# labwiz-module_t420-v0_2.net
KiCad netlist of a schematic drawn in EAGLE
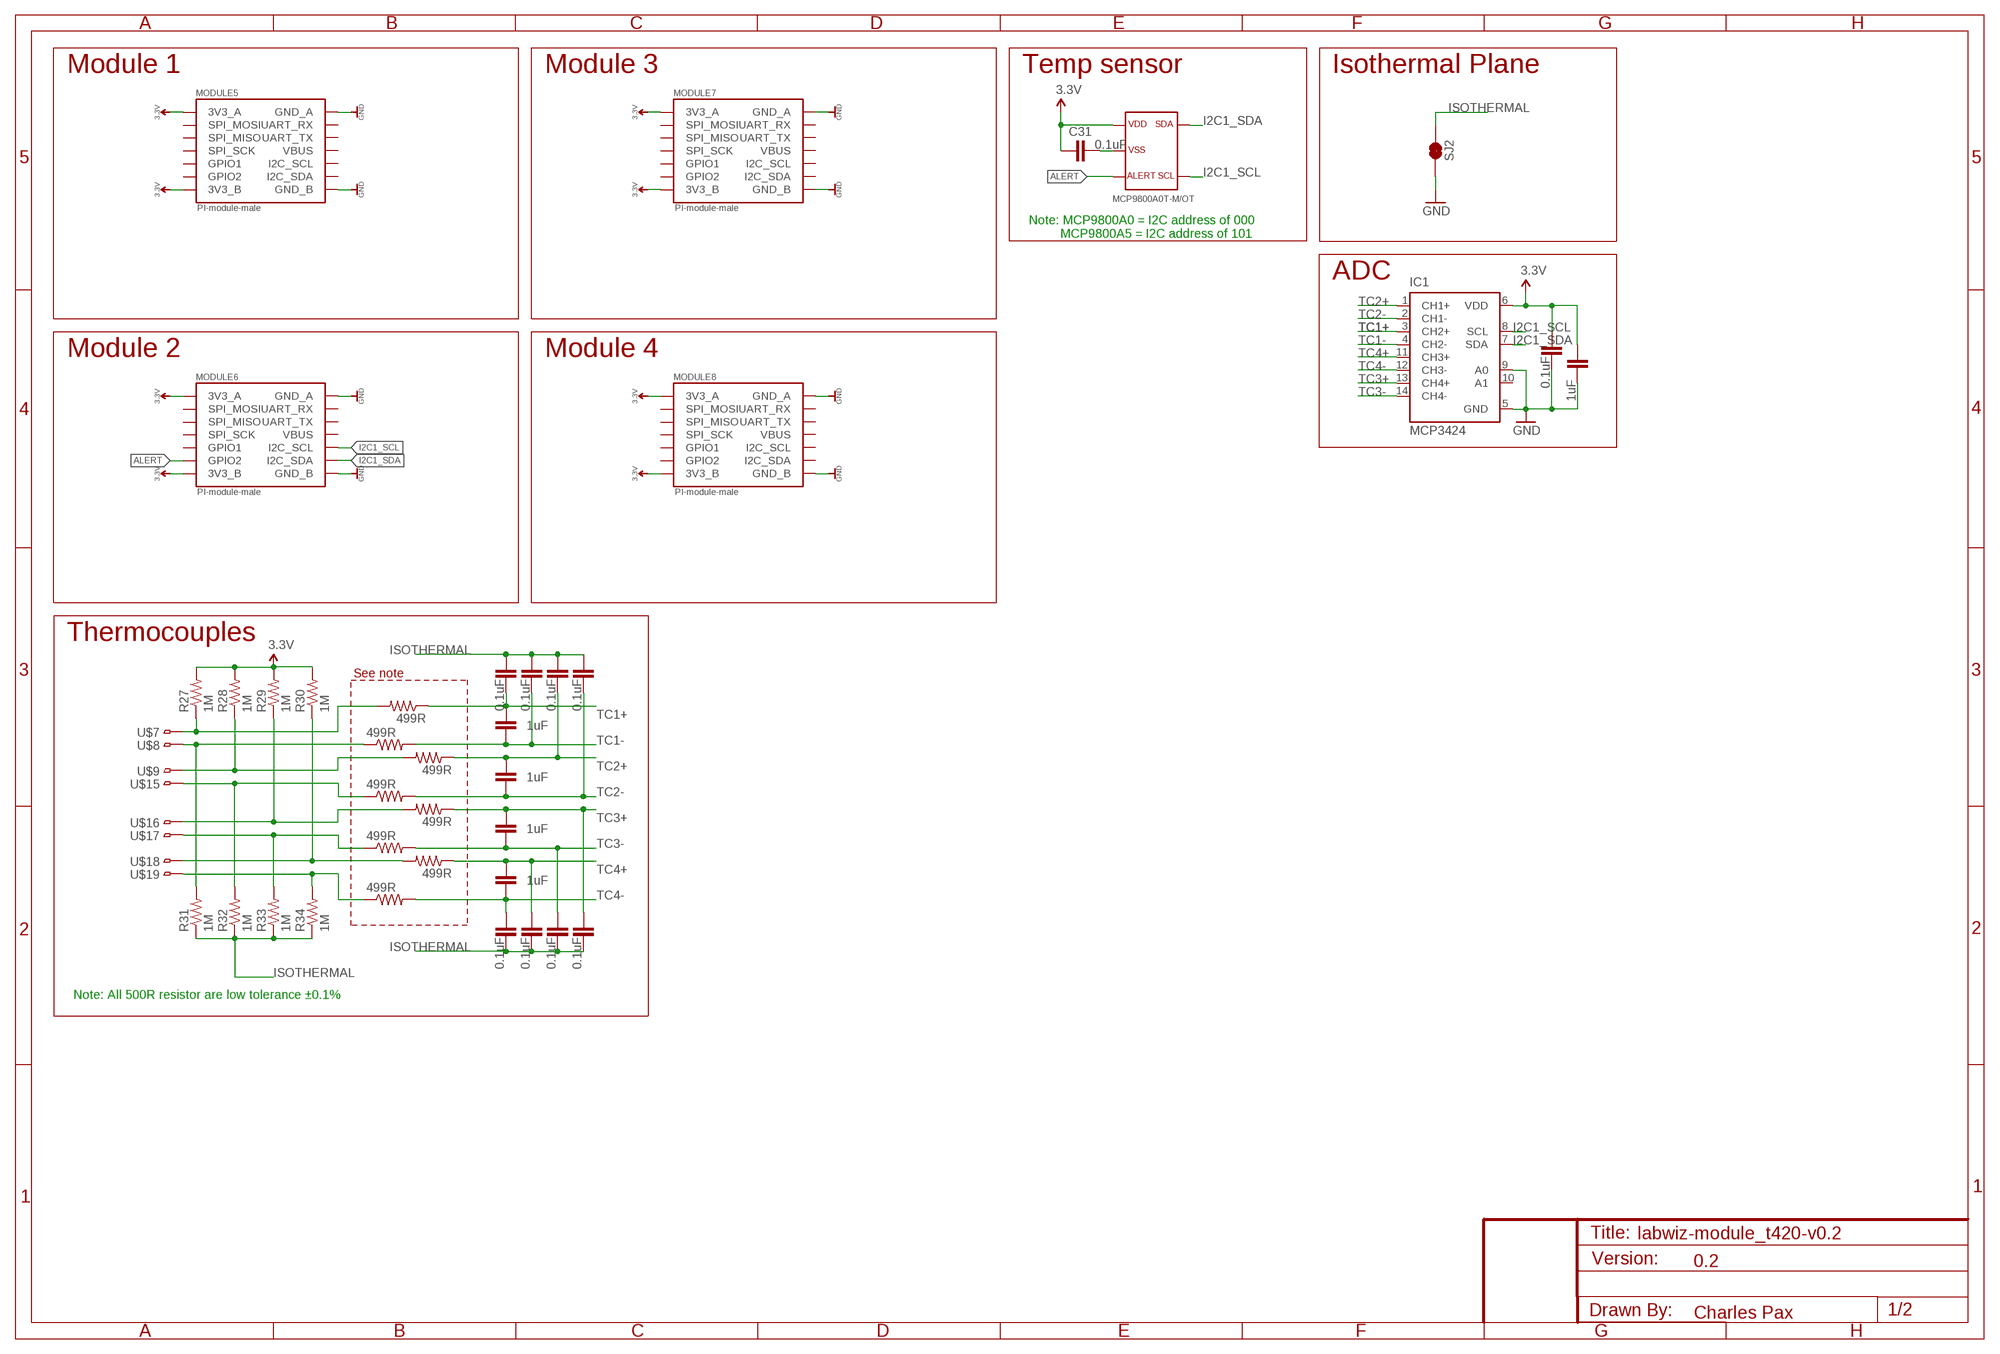
[diagram p0: schematic, sheet 1]

(export (version "E")
  (design (tool "Eeschema 10.0.6"))
  (components
    (comp (ref "C7")
      (value "1uF")
      (footprint "eagle-import:SPARKFUN-CAPACITORS_0603-CAP")
      (libsource (lib "eagle-import") (part "SPARKFUN-CAPACITORS_CAP0603-CAP"))
    )
    (comp (ref "C8")
      (value "1uF")
      (footprint "eagle-import:SPARKFUN-CAPACITORS_0603-CAP")
      (libsource (lib "eagle-import") (part "SPARKFUN-CAPACITORS_CAP0603-CAP"))
    )
    (comp (ref "C10")
      (value "1uF")
      (footprint "eagle-import:SPARKFUN-CAPACITORS_0603-CAP")
      (libsource (lib "eagle-import") (part "SPARKFUN-CAPACITORS_CAP0603-CAP"))
    )
    (comp (ref "C11")
      (value "1uF")
      (footprint "eagle-import:SPARKFUN-CAPACITORS_0603-CAP")
      (libsource (lib "eagle-import") (part "SPARKFUN-CAPACITORS_CAP0603-CAP"))
    )
    (comp (ref "C13")
      (value "0.1uF")
      (footprint "eagle-import:SPARKFUN-CAPACITORS_0603-CAP")
      (libsource (lib "eagle-import") (part "SPARKFUN-CAPACITORS_CAP0603-CAP"))
    )
    (comp (ref "C14")
      (value "0.1uF")
      (footprint "eagle-import:SPARKFUN-CAPACITORS_0603-CAP")
      (libsource (lib "eagle-import") (part "SPARKFUN-CAPACITORS_CAP0603-CAP"))
    )
    (comp (ref "C15")
      (value "0.1uF")
      (footprint "eagle-import:SPARKFUN-CAPACITORS_0603-CAP")
      (libsource (lib "eagle-import") (part "SPARKFUN-CAPACITORS_CAP0603-CAP"))
    )
    (comp (ref "C16")
      (value "0.1uF")
      (footprint "eagle-import:SPARKFUN-CAPACITORS_0603-CAP")
      (libsource (lib "eagle-import") (part "SPARKFUN-CAPACITORS_CAP0603-CAP"))
    )
    (comp (ref "C17")
      (value "0.1uF")
      (footprint "eagle-import:SPARKFUN-CAPACITORS_0603-CAP")
      (libsource (lib "eagle-import") (part "SPARKFUN-CAPACITORS_CAP0603-CAP"))
    )
    (comp (ref "C24")
      (value "0.1uF")
      (footprint "eagle-import:SPARKFUN-CAPACITORS_0603-CAP")
      (libsource (lib "eagle-import") (part "SPARKFUN-CAPACITORS_CAP0603-CAP"))
    )
    (comp (ref "C25")
      (value "0.1uF")
      (footprint "eagle-import:SPARKFUN-CAPACITORS_0603-CAP")
      (libsource (lib "eagle-import") (part "SPARKFUN-CAPACITORS_CAP0603-CAP"))
    )
    (comp (ref "C29")
      (value "0.1uF")
      (footprint "eagle-import:SPARKFUN-CAPACITORS_0603-CAP")
      (libsource (lib "eagle-import") (part "SPARKFUN-CAPACITORS_CAP0603-CAP"))
    )
    (comp (ref "C30")
      (value "1uF")
      (footprint "eagle-import:SPARKFUN-CAPACITORS_0603-CAP")
      (libsource (lib "eagle-import") (part "SPARKFUN-CAPACITORS_CAP0603-CAP"))
    )
    (comp (ref "C31")
      (value "0.1uF")
      (footprint "eagle-import:SPARKFUN-CAPACITORS_0603-CAP")
      (libsource (lib "eagle-import") (part "SPARKFUN-CAPACITORS_CAP0603-CAP"))
    )
    (comp (ref "C37")
      (value "0.1uF")
      (footprint "eagle-import:SPARKFUN-CAPACITORS_0603-CAP")
      (libsource (lib "eagle-import") (part "SPARKFUN-CAPACITORS_CAP0603-CAP"))
    )
    (comp (ref "IC1")
      (value "MCP3424")
      (footprint "eagle-import:SO14")
      (fields (field (name "MF") "Microchip Technology") (field (name "MPN") "MCP3424-E/SL"))
      (libsource (lib "eagle-import") (part "MCP3424"))
    )
    (comp (ref "MODULE5")
      (value "PI-module-male")
      (footprint "eagle-import:M07X2_2MM_EDGE")
      (fields (field (name "MF") "Pax Instruments") (field (name "MPN") "PIxxxx"))
      (libsource (lib "eagle-import") (part "PAX_MODULE_EDGE_MALE_MODULE"))
    )
    (comp (ref "MODULE6")
      (value "PI-module-male")
      (footprint "eagle-import:M07X2_2MM_EDGE")
      (fields (field (name "MF") "Pax Instruments") (field (name "MPN") "PIxxxx"))
      (libsource (lib "eagle-import") (part "PAX_MODULE_EDGE_MALE_MODULE"))
    )
    (comp (ref "MODULE7")
      (value "PI-module-male")
      (footprint "eagle-import:M07X2_2MM_EDGE")
      (fields (field (name "MF") "Pax Instruments") (field (name "MPN") "PIxxxx"))
      (libsource (lib "eagle-import") (part "PAX_MODULE_EDGE_MALE_MODULE"))
    )
    (comp (ref "MODULE8")
      (value "PI-module-male")
      (footprint "eagle-import:M07X2_2MM_EDGE")
      (fields (field (name "MF") "Pax Instruments") (field (name "MPN") "PIxxxx"))
      (libsource (lib "eagle-import") (part "PAX_MODULE_EDGE_MALE_MODULE"))
    )
    (comp (ref "R27")
      (value "1M")
      (footprint "eagle-import:SPARKFUN-RESISTORS_0603-RES")
      (libsource (lib "eagle-import") (part "SPARKFUN-RESISTORS_RESISTOR0603-RES"))
    )
    (comp (ref "R28")
      (value "1M")
      (footprint "eagle-import:SPARKFUN-RESISTORS_0603-RES")
      (libsource (lib "eagle-import") (part "SPARKFUN-RESISTORS_RESISTOR0603-RES"))
    )
    (comp (ref "R29")
      (value "1M")
      (footprint "eagle-import:SPARKFUN-RESISTORS_0603-RES")
      (libsource (lib "eagle-import") (part "SPARKFUN-RESISTORS_RESISTOR0603-RES"))
    )
    (comp (ref "R30")
      (value "1M")
      (footprint "eagle-import:SPARKFUN-RESISTORS_0603-RES")
      (libsource (lib "eagle-import") (part "SPARKFUN-RESISTORS_RESISTOR0603-RES"))
    )
    (comp (ref "R31")
      (value "1M")
      (footprint "eagle-import:SPARKFUN-RESISTORS_0603-RES")
      (libsource (lib "eagle-import") (part "SPARKFUN-RESISTORS_RESISTOR0603-RES"))
    )
    (comp (ref "R32")
      (value "1M")
      (footprint "eagle-import:SPARKFUN-RESISTORS_0603-RES")
      (libsource (lib "eagle-import") (part "SPARKFUN-RESISTORS_RESISTOR0603-RES"))
    )
    (comp (ref "R33")
      (value "1M")
      (footprint "eagle-import:SPARKFUN-RESISTORS_0603-RES")
      (libsource (lib "eagle-import") (part "SPARKFUN-RESISTORS_RESISTOR0603-RES"))
    )
    (comp (ref "R34")
      (value "1M")
      (footprint "eagle-import:SPARKFUN-RESISTORS_0603-RES")
      (libsource (lib "eagle-import") (part "SPARKFUN-RESISTORS_RESISTOR0603-RES"))
    )
    (comp (ref "R35")
      (value "499R")
      (footprint "eagle-import:SPARKFUN-RESISTORS_0603-RES")
      (fields (field (name "MF") "Vishay") (field (name "MPN") "TNPW0603499RBEEA"))
      (libsource (lib "eagle-import") (part "SPARKFUN-RESISTORS_RESISTOR0603-RES"))
    )
    (comp (ref "R36")
      (value "499R")
      (footprint "eagle-import:SPARKFUN-RESISTORS_0603-RES")
      (fields (field (name "MF") "Vishay") (field (name "MPN") "TNPW0603499RBEEA"))
      (libsource (lib "eagle-import") (part "SPARKFUN-RESISTORS_RESISTOR0603-RES"))
    )
    (comp (ref "R37")
      (value "499R")
      (footprint "eagle-import:SPARKFUN-RESISTORS_0603-RES")
      (fields (field (name "MF") "Vishay") (field (name "MPN") "TNPW0603499RBEEA"))
      (libsource (lib "eagle-import") (part "SPARKFUN-RESISTORS_RESISTOR0603-RES"))
    )
    (comp (ref "R38")
      (value "499R")
      (footprint "eagle-import:SPARKFUN-RESISTORS_0603-RES")
      (fields (field (name "MF") "Vishay") (field (name "MPN") "TNPW0603499RBEEA"))
      (libsource (lib "eagle-import") (part "SPARKFUN-RESISTORS_RESISTOR0603-RES"))
    )
    (comp (ref "R39")
      (value "499R")
      (footprint "eagle-import:SPARKFUN-RESISTORS_0603-RES")
      (fields (field (name "MF") "Vishay") (field (name "MPN") "TNPW0603499RBEEA"))
      (libsource (lib "eagle-import") (part "SPARKFUN-RESISTORS_RESISTOR0603-RES"))
    )
    (comp (ref "R40")
      (value "499R")
      (footprint "eagle-import:SPARKFUN-RESISTORS_0603-RES")
      (fields (field (name "MF") "Vishay") (field (name "MPN") "TNPW0603499RBEEA"))
      (libsource (lib "eagle-import") (part "SPARKFUN-RESISTORS_RESISTOR0603-RES"))
    )
    (comp (ref "R41")
      (value "499R")
      (footprint "eagle-import:SPARKFUN-RESISTORS_0603-RES")
      (fields (field (name "MF") "Vishay") (field (name "MPN") "TNPW0603499RBEEA"))
      (libsource (lib "eagle-import") (part "SPARKFUN-RESISTORS_RESISTOR0603-RES"))
    )
    (comp (ref "R42")
      (value "499R")
      (footprint "eagle-import:SPARKFUN-RESISTORS_0603-RES")
      (fields (field (name "MF") "Vishay") (field (name "MPN") "TNPW0603499RBEEA"))
      (libsource (lib "eagle-import") (part "SPARKFUN-RESISTORS_RESISTOR0603-RES"))
    )
    (comp (ref "SJ2")
      (value "JUMPER-PAD-2-NC_BY_TRACE")
      (footprint "eagle-import:PAD-JUMPER-2-NC_BY_TRACE_YES_SILK")
      (libsource (lib "eagle-import") (part "JUMPER-PAD-2-NC_BY_TRACE"))
    )
    (comp (ref "U$7")
      (value "TC-MINI-SINGLE")
      (footprint "eagle-import:TC-CLIP-SINGLE")
      (fields (field (name "MF") "Pax Instrument") (field (name "MPN") "Thermo-clip2"))
      (libsource (lib "eagle-import") (part "TC-MINI-SINGLE"))
    )
    (comp (ref "U$8")
      (value "TC-MINI-SINGLE")
      (footprint "eagle-import:TC-CLIP-SINGLE")
      (fields (field (name "MF") "Pax Instrument") (field (name "MPN") "Thermo-clip2"))
      (libsource (lib "eagle-import") (part "TC-MINI-SINGLE"))
    )
    (comp (ref "U$9")
      (value "TC-MINI-SINGLE")
      (footprint "eagle-import:TC-CLIP-SINGLE")
      (fields (field (name "MF") "Pax Instrument") (field (name "MPN") "Thermo-clip2"))
      (libsource (lib "eagle-import") (part "TC-MINI-SINGLE"))
    )
    (comp (ref "U$15")
      (value "TC-MINI-SINGLE")
      (footprint "eagle-import:TC-CLIP-SINGLE")
      (fields (field (name "MF") "Pax Instrument") (field (name "MPN") "Thermo-clip2"))
      (libsource (lib "eagle-import") (part "TC-MINI-SINGLE"))
    )
    (comp (ref "U$16")
      (value "TC-MINI-SINGLE")
      (footprint "eagle-import:TC-CLIP-SINGLE")
      (fields (field (name "MF") "Pax Instrument") (field (name "MPN") "Thermo-clip2"))
      (libsource (lib "eagle-import") (part "TC-MINI-SINGLE"))
    )
    (comp (ref "U$17")
      (value "TC-MINI-SINGLE")
      (footprint "eagle-import:TC-CLIP-SINGLE")
      (fields (field (name "MF") "Pax Instrument") (field (name "MPN") "Thermo-clip2"))
      (libsource (lib "eagle-import") (part "TC-MINI-SINGLE"))
    )
    (comp (ref "U$18")
      (value "TC-MINI-SINGLE")
      (footprint "eagle-import:TC-CLIP-SINGLE")
      (fields (field (name "MF") "Pax Instrument") (field (name "MPN") "Thermo-clip2"))
      (libsource (lib "eagle-import") (part "TC-MINI-SINGLE"))
    )
    (comp (ref "U$19")
      (value "TC-MINI-SINGLE")
      (footprint "eagle-import:TC-CLIP-SINGLE")
      (fields (field (name "MF") "Pax Instrument") (field (name "MPN") "Thermo-clip2"))
      (libsource (lib "eagle-import") (part "TC-MINI-SINGLE"))
    )
    (comp (ref "U1")
      (value "MCP9800")
      (footprint "eagle-import:SOT23-5L")
      (fields (field (name "MF") "Microchip Technology") (field (name "MPN") "MCP9800A0T-M/OT"))
      (libsource (lib "eagle-import") (part "MCP9800"))
    )
  )
  (nets
    (net (code "1") (name "3.3V") (class "Default")
      (node (ref "C29") (pin "1") (pinfunction "1_1") (pintype "passive"))
      (node (ref "C30") (pin "1") (pinfunction "1_1") (pintype "passive"))
      (node (ref "C31") (pin "1") (pinfunction "1_1") (pintype "passive"))
      (node (ref "IC1") (pin "6") (pinfunction "VDD_6") (pintype "power_in"))
      (node (ref "MODULE5") (pin "P$1") (pinfunction "3V3_B_P$1") (pintype "bidirectional"))
      (node (ref "MODULE5") (pin "P$13") (pinfunction "3V3_A_P$13") (pintype "power_in"))
      (node (ref "MODULE6") (pin "P$1") (pinfunction "3V3_B_P$1") (pintype "bidirectional"))
      (node (ref "MODULE6") (pin "P$13") (pinfunction "3V3_A_P$13") (pintype "power_in"))
      (node (ref "MODULE7") (pin "P$1") (pinfunction "3V3_B_P$1") (pintype "bidirectional"))
      (node (ref "MODULE7") (pin "P$13") (pinfunction "3V3_A_P$13") (pintype "power_in"))
      (node (ref "MODULE8") (pin "P$1") (pinfunction "3V3_B_P$1") (pintype "bidirectional"))
      (node (ref "MODULE8") (pin "P$13") (pinfunction "3V3_A_P$13") (pintype "power_in"))
      (node (ref "R27") (pin "2") (pinfunction "2_2") (pintype "passive"))
      (node (ref "R28") (pin "2") (pinfunction "2_2") (pintype "passive"))
      (node (ref "R29") (pin "2") (pinfunction "2_2") (pintype "passive"))
      (node (ref "R30") (pin "2") (pinfunction "2_2") (pintype "passive"))
      (node (ref "U1") (pin "1") (pinfunction "1_1") (pintype "bidirectional"))
    )
    (net (code "2") (name "ALERT") (class "Default")
      (node (ref "MODULE6") (pin "P$3") (pinfunction "GPIO2_P$3") (pintype "bidirectional"))
      (node (ref "U1") (pin "3") (pinfunction "3_3") (pintype "bidirectional"))
    )
    (net (code "3") (name "GND") (class "Default")
      (node (ref "C29") (pin "2") (pinfunction "2_2") (pintype "passive"))
      (node (ref "C30") (pin "2") (pinfunction "2_2") (pintype "passive"))
      (node (ref "IC1") (pin "5") (pinfunction "GND_5") (pintype "power_in"))
      (node (ref "IC1") (pin "9") (pinfunction "A0_9") (pintype "input"))
      (node (ref "MODULE5") (pin "P$14") (pinfunction "GND_A_P$14") (pintype "power_in"))
      (node (ref "MODULE5") (pin "P$2") (pinfunction "GND_B_P$2") (pintype "bidirectional"))
      (node (ref "MODULE6") (pin "P$14") (pinfunction "GND_A_P$14") (pintype "power_in"))
      (node (ref "MODULE6") (pin "P$2") (pinfunction "GND_B_P$2") (pintype "bidirectional"))
      (node (ref "MODULE7") (pin "P$14") (pinfunction "GND_A_P$14") (pintype "power_in"))
      (node (ref "MODULE7") (pin "P$2") (pinfunction "GND_B_P$2") (pintype "bidirectional"))
      (node (ref "MODULE8") (pin "P$14") (pinfunction "GND_A_P$14") (pintype "power_in"))
      (node (ref "MODULE8") (pin "P$2") (pinfunction "GND_B_P$2") (pintype "bidirectional"))
      (node (ref "SJ2") (pin "1") (pinfunction "1_1") (pintype "passive"))
    )
    (net (code "4") (name "I2C1_SCL") (class "Default")
      (node (ref "IC1") (pin "8") (pinfunction "SCL_8") (pintype "input"))
      (node (ref "MODULE6") (pin "P$6") (pinfunction "I2C_SCL_P$6") (pintype "bidirectional"))
      (node (ref "U1") (pin "4") (pinfunction "4_4") (pintype "bidirectional"))
    )
    (net (code "5") (name "I2C1_SDA") (class "Default")
      (node (ref "IC1") (pin "7") (pinfunction "SDA_7") (pintype "bidirectional"))
      (node (ref "MODULE6") (pin "P$4") (pinfunction "I2C_SDA_P$4") (pintype "bidirectional"))
      (node (ref "U1") (pin "5") (pinfunction "5_5") (pintype "bidirectional"))
    )
    (net (code "6") (name "ISOTHERMAL") (class "Default")
      (node (ref "C13") (pin "2") (pinfunction "2_2") (pintype "passive"))
      (node (ref "C14") (pin "2") (pinfunction "2_2") (pintype "passive"))
      (node (ref "C15") (pin "2") (pinfunction "2_2") (pintype "passive"))
      (node (ref "C16") (pin "2") (pinfunction "2_2") (pintype "passive"))
      (node (ref "C17") (pin "1") (pinfunction "1_1") (pintype "passive"))
      (node (ref "C24") (pin "1") (pinfunction "1_1") (pintype "passive"))
      (node (ref "C25") (pin "1") (pinfunction "1_1") (pintype "passive"))
      (node (ref "C31") (pin "2") (pinfunction "2_2") (pintype "passive"))
      (node (ref "C37") (pin "1") (pinfunction "1_1") (pintype "passive"))
      (node (ref "R31") (pin "1") (pinfunction "1_1") (pintype "passive"))
      (node (ref "R32") (pin "1") (pinfunction "1_1") (pintype "passive"))
      (node (ref "R33") (pin "1") (pinfunction "1_1") (pintype "passive"))
      (node (ref "R34") (pin "1") (pinfunction "1_1") (pintype "passive"))
      (node (ref "SJ2") (pin "2") (pinfunction "2_2") (pintype "passive"))
      (node (ref "U1") (pin "2") (pinfunction "2_2") (pintype "bidirectional"))
    )
    (net (code "7") (name "Net-(U$7-1)") (class "Default")
      (node (ref "R27") (pin "1") (pinfunction "1_1") (pintype "passive"))
      (node (ref "R35") (pin "2") (pinfunction "2_2") (pintype "passive"))
      (node (ref "U$7") (pin "P$1") (pinfunction "1_P$1") (pintype "passive"))
    )
    (net (code "8") (name "Net-(U$8-1)") (class "Default")
      (node (ref "R31") (pin "2") (pinfunction "2_2") (pintype "passive"))
      (node (ref "R36") (pin "1") (pinfunction "1_1") (pintype "passive"))
      (node (ref "U$8") (pin "P$1") (pinfunction "1_P$1") (pintype "passive"))
    )
    (net (code "9") (name "Net-(U$9-1)") (class "Default")
      (node (ref "R28") (pin "1") (pinfunction "1_1") (pintype "passive"))
      (node (ref "R37") (pin "2") (pinfunction "2_2") (pintype "passive"))
      (node (ref "U$9") (pin "P$1") (pinfunction "1_P$1") (pintype "passive"))
    )
    (net (code "10") (name "Net-(U$15-1)") (class "Default")
      (node (ref "R32") (pin "2") (pinfunction "2_2") (pintype "passive"))
      (node (ref "R38") (pin "1") (pinfunction "1_1") (pintype "passive"))
      (node (ref "U$15") (pin "P$1") (pinfunction "1_P$1") (pintype "passive"))
    )
    (net (code "11") (name "Net-(U$16-1)") (class "Default")
      (node (ref "R29") (pin "1") (pinfunction "1_1") (pintype "passive"))
      (node (ref "R39") (pin "2") (pinfunction "2_2") (pintype "passive"))
      (node (ref "U$16") (pin "P$1") (pinfunction "1_P$1") (pintype "passive"))
    )
    (net (code "12") (name "Net-(U$17-1)") (class "Default")
      (node (ref "R33") (pin "2") (pinfunction "2_2") (pintype "passive"))
      (node (ref "R41") (pin "1") (pinfunction "1_1") (pintype "passive"))
      (node (ref "U$17") (pin "P$1") (pinfunction "1_P$1") (pintype "passive"))
    )
    (net (code "13") (name "Net-(U$18-1)") (class "Default")
      (node (ref "R30") (pin "1") (pinfunction "1_1") (pintype "passive"))
      (node (ref "R40") (pin "2") (pinfunction "2_2") (pintype "passive"))
      (node (ref "U$18") (pin "P$1") (pinfunction "1_P$1") (pintype "passive"))
    )
    (net (code "14") (name "Net-(U$19-1)") (class "Default")
      (node (ref "R34") (pin "2") (pinfunction "2_2") (pintype "passive"))
      (node (ref "R42") (pin "1") (pinfunction "1_1") (pintype "passive"))
      (node (ref "U$19") (pin "P$1") (pinfunction "1_P$1") (pintype "passive"))
    )
    (net (code "15") (name "TC1+") (class "Default")
      (node (ref "C17") (pin "2") (pinfunction "2_2") (pintype "passive"))
      (node (ref "C7") (pin "1") (pinfunction "1_1") (pintype "passive"))
      (node (ref "IC1") (pin "3") (pinfunction "CH2+_3") (pintype "input"))
      (node (ref "R35") (pin "1") (pinfunction "1_1") (pintype "passive"))
    )
    (net (code "16") (name "TC1-") (class "Default")
      (node (ref "C24") (pin "2") (pinfunction "2_2") (pintype "passive"))
      (node (ref "C7") (pin "2") (pinfunction "2_2") (pintype "passive"))
      (node (ref "IC1") (pin "4") (pinfunction "CH2-_4") (pintype "input"))
      (node (ref "R36") (pin "2") (pinfunction "2_2") (pintype "passive"))
    )
    (net (code "17") (name "TC2+") (class "Default")
      (node (ref "C25") (pin "2") (pinfunction "2_2") (pintype "passive"))
      (node (ref "C8") (pin "1") (pinfunction "1_1") (pintype "passive"))
      (node (ref "IC1") (pin "1") (pinfunction "CH1+_1") (pintype "input"))
      (node (ref "R37") (pin "1") (pinfunction "1_1") (pintype "passive"))
    )
    (net (code "18") (name "TC2-") (class "Default")
      (node (ref "C37") (pin "2") (pinfunction "2_2") (pintype "passive"))
      (node (ref "C8") (pin "2") (pinfunction "2_2") (pintype "passive"))
      (node (ref "IC1") (pin "2") (pinfunction "CH1-_2") (pintype "input"))
      (node (ref "R38") (pin "2") (pinfunction "2_2") (pintype "passive"))
    )
    (net (code "19") (name "TC3+") (class "Default")
      (node (ref "C10") (pin "1") (pinfunction "1_1") (pintype "passive"))
      (node (ref "C16") (pin "1") (pinfunction "1_1") (pintype "passive"))
      (node (ref "IC1") (pin "13") (pinfunction "CH4+_13") (pintype "input"))
      (node (ref "R39") (pin "1") (pinfunction "1_1") (pintype "passive"))
    )
    (net (code "20") (name "TC3-") (class "Default")
      (node (ref "C10") (pin "2") (pinfunction "2_2") (pintype "passive"))
      (node (ref "C15") (pin "1") (pinfunction "1_1") (pintype "passive"))
      (node (ref "IC1") (pin "14") (pinfunction "CH4-_14") (pintype "input"))
      (node (ref "R41") (pin "2") (pinfunction "2_2") (pintype "passive"))
    )
    (net (code "21") (name "TC4+") (class "Default")
      (node (ref "C11") (pin "1") (pinfunction "1_1") (pintype "passive"))
      (node (ref "C14") (pin "1") (pinfunction "1_1") (pintype "passive"))
      (node (ref "IC1") (pin "11") (pinfunction "CH3+_11") (pintype "input"))
      (node (ref "R40") (pin "1") (pinfunction "1_1") (pintype "passive"))
    )
    (net (code "22") (name "TC4-") (class "Default")
      (node (ref "C11") (pin "2") (pinfunction "2_2") (pintype "passive"))
      (node (ref "C13") (pin "1") (pinfunction "1_1") (pintype "passive"))
      (node (ref "IC1") (pin "12") (pinfunction "CH3-_12") (pintype "input"))
      (node (ref "R42") (pin "2") (pinfunction "2_2") (pintype "passive"))
    )
    (net (code "23") (name "unconnected-(IC1-A1-Pad10)") (class "Default")
      (node (ref "IC1") (pin "10") (pinfunction "A1_10") (pintype "input"))
    )
    (net (code "24") (name "unconnected-(MODULE5-GPIO1-PadP$5)") (class "Default")
      (node (ref "MODULE5") (pin "P$5") (pinfunction "GPIO1_P$5") (pintype "bidirectional"))
    )
    (net (code "25") (name "unconnected-(MODULE5-GPIO2-PadP$3)") (class "Default")
      (node (ref "MODULE5") (pin "P$3") (pinfunction "GPIO2_P$3") (pintype "bidirectional"))
    )
    (net (code "26") (name "unconnected-(MODULE5-I2C_SCL-PadP$6)") (class "Default")
      (node (ref "MODULE5") (pin "P$6") (pinfunction "I2C_SCL_P$6") (pintype "bidirectional"))
    )
    (net (code "27") (name "unconnected-(MODULE5-I2C_SDA-PadP$4)") (class "Default")
      (node (ref "MODULE5") (pin "P$4") (pinfunction "I2C_SDA_P$4") (pintype "bidirectional"))
    )
    (net (code "28") (name "unconnected-(MODULE5-SPI_MISO-PadP$9)") (class "Default")
      (node (ref "MODULE5") (pin "P$9") (pinfunction "SPI_MISO_P$9") (pintype "bidirectional"))
    )
    (net (code "29") (name "unconnected-(MODULE5-SPI_MOSI-PadP$11)") (class "Default")
      (node (ref "MODULE5") (pin "P$11") (pinfunction "SPI_MOSI_P$11") (pintype "bidirectional"))
    )
    (net (code "30") (name "unconnected-(MODULE5-SPI_SCK-PadP$7)") (class "Default")
      (node (ref "MODULE5") (pin "P$7") (pinfunction "SPI_SCK_P$7") (pintype "bidirectional"))
    )
    (net (code "31") (name "unconnected-(MODULE5-UART_RX-PadP$12)") (class "Default")
      (node (ref "MODULE5") (pin "P$12") (pinfunction "UART_RX_P$12") (pintype "bidirectional"))
    )
    (net (code "32") (name "unconnected-(MODULE5-UART_TX-PadP$10)") (class "Default")
      (node (ref "MODULE5") (pin "P$10") (pinfunction "UART_TX_P$10") (pintype "bidirectional"))
    )
    (net (code "33") (name "unconnected-(MODULE5-VBUS-PadP$8)") (class "Default")
      (node (ref "MODULE5") (pin "P$8") (pinfunction "VBUS_P$8") (pintype "bidirectional"))
    )
    (net (code "34") (name "unconnected-(MODULE6-GPIO1-PadP$5)") (class "Default")
      (node (ref "MODULE6") (pin "P$5") (pinfunction "GPIO1_P$5") (pintype "bidirectional"))
    )
    (net (code "35") (name "unconnected-(MODULE6-SPI_MISO-PadP$9)") (class "Default")
      (node (ref "MODULE6") (pin "P$9") (pinfunction "SPI_MISO_P$9") (pintype "bidirectional"))
    )
    (net (code "36") (name "unconnected-(MODULE6-SPI_MOSI-PadP$11)") (class "Default")
      (node (ref "MODULE6") (pin "P$11") (pinfunction "SPI_MOSI_P$11") (pintype "bidirectional"))
    )
    (net (code "37") (name "unconnected-(MODULE6-SPI_SCK-PadP$7)") (class "Default")
      (node (ref "MODULE6") (pin "P$7") (pinfunction "SPI_SCK_P$7") (pintype "bidirectional"))
    )
    (net (code "38") (name "unconnected-(MODULE6-UART_RX-PadP$12)") (class "Default")
      (node (ref "MODULE6") (pin "P$12") (pinfunction "UART_RX_P$12") (pintype "bidirectional"))
    )
    (net (code "39") (name "unconnected-(MODULE6-UART_TX-PadP$10)") (class "Default")
      (node (ref "MODULE6") (pin "P$10") (pinfunction "UART_TX_P$10") (pintype "bidirectional"))
    )
    (net (code "40") (name "unconnected-(MODULE6-VBUS-PadP$8)") (class "Default")
      (node (ref "MODULE6") (pin "P$8") (pinfunction "VBUS_P$8") (pintype "bidirectional"))
    )
    (net (code "41") (name "unconnected-(MODULE7-GPIO1-PadP$5)") (class "Default")
      (node (ref "MODULE7") (pin "P$5") (pinfunction "GPIO1_P$5") (pintype "bidirectional"))
    )
    (net (code "42") (name "unconnected-(MODULE7-GPIO2-PadP$3)") (class "Default")
      (node (ref "MODULE7") (pin "P$3") (pinfunction "GPIO2_P$3") (pintype "bidirectional"))
    )
    (net (code "43") (name "unconnected-(MODULE7-I2C_SCL-PadP$6)") (class "Default")
      (node (ref "MODULE7") (pin "P$6") (pinfunction "I2C_SCL_P$6") (pintype "bidirectional"))
    )
    (net (code "44") (name "unconnected-(MODULE7-I2C_SDA-PadP$4)") (class "Default")
      (node (ref "MODULE7") (pin "P$4") (pinfunction "I2C_SDA_P$4") (pintype "bidirectional"))
    )
    (net (code "45") (name "unconnected-(MODULE7-SPI_MISO-PadP$9)") (class "Default")
      (node (ref "MODULE7") (pin "P$9") (pinfunction "SPI_MISO_P$9") (pintype "bidirectional"))
    )
    (net (code "46") (name "unconnected-(MODULE7-SPI_MOSI-PadP$11)") (class "Default")
      (node (ref "MODULE7") (pin "P$11") (pinfunction "SPI_MOSI_P$11") (pintype "bidirectional"))
    )
    (net (code "47") (name "unconnected-(MODULE7-SPI_SCK-PadP$7)") (class "Default")
      (node (ref "MODULE7") (pin "P$7") (pinfunction "SPI_SCK_P$7") (pintype "bidirectional"))
    )
    (net (code "48") (name "unconnected-(MODULE7-UART_RX-PadP$12)") (class "Default")
      (node (ref "MODULE7") (pin "P$12") (pinfunction "UART_RX_P$12") (pintype "bidirectional"))
    )
    (net (code "49") (name "unconnected-(MODULE7-UART_TX-PadP$10)") (class "Default")
      (node (ref "MODULE7") (pin "P$10") (pinfunction "UART_TX_P$10") (pintype "bidirectional"))
    )
    (net (code "50") (name "unconnected-(MODULE7-VBUS-PadP$8)") (class "Default")
      (node (ref "MODULE7") (pin "P$8") (pinfunction "VBUS_P$8") (pintype "bidirectional"))
    )
    (net (code "51") (name "unconnected-(MODULE8-GPIO1-PadP$5)") (class "Default")
      (node (ref "MODULE8") (pin "P$5") (pinfunction "GPIO1_P$5") (pintype "bidirectional"))
    )
    (net (code "52") (name "unconnected-(MODULE8-GPIO2-PadP$3)") (class "Default")
      (node (ref "MODULE8") (pin "P$3") (pinfunction "GPIO2_P$3") (pintype "bidirectional"))
    )
    (net (code "53") (name "unconnected-(MODULE8-I2C_SCL-PadP$6)") (class "Default")
      (node (ref "MODULE8") (pin "P$6") (pinfunction "I2C_SCL_P$6") (pintype "bidirectional"))
    )
    (net (code "54") (name "unconnected-(MODULE8-I2C_SDA-PadP$4)") (class "Default")
      (node (ref "MODULE8") (pin "P$4") (pinfunction "I2C_SDA_P$4") (pintype "bidirectional"))
    )
    (net (code "55") (name "unconnected-(MODULE8-SPI_MISO-PadP$9)") (class "Default")
      (node (ref "MODULE8") (pin "P$9") (pinfunction "SPI_MISO_P$9") (pintype "bidirectional"))
    )
    (net (code "56") (name "unconnected-(MODULE8-SPI_MOSI-PadP$11)") (class "Default")
      (node (ref "MODULE8") (pin "P$11") (pinfunction "SPI_MOSI_P$11") (pintype "bidirectional"))
    )
    (net (code "57") (name "unconnected-(MODULE8-SPI_SCK-PadP$7)") (class "Default")
      (node (ref "MODULE8") (pin "P$7") (pinfunction "SPI_SCK_P$7") (pintype "bidirectional"))
    )
    (net (code "58") (name "unconnected-(MODULE8-UART_RX-PadP$12)") (class "Default")
      (node (ref "MODULE8") (pin "P$12") (pinfunction "UART_RX_P$12") (pintype "bidirectional"))
    )
    (net (code "59") (name "unconnected-(MODULE8-UART_TX-PadP$10)") (class "Default")
      (node (ref "MODULE8") (pin "P$10") (pinfunction "UART_TX_P$10") (pintype "bidirectional"))
    )
    (net (code "60") (name "unconnected-(MODULE8-VBUS-PadP$8)") (class "Default")
      (node (ref "MODULE8") (pin "P$8") (pinfunction "VBUS_P$8") (pintype "bidirectional"))
    )
  )
)
